# INPUT_OUTPUT.net
KiCad netlist of a schematic drawn in Altium Designer
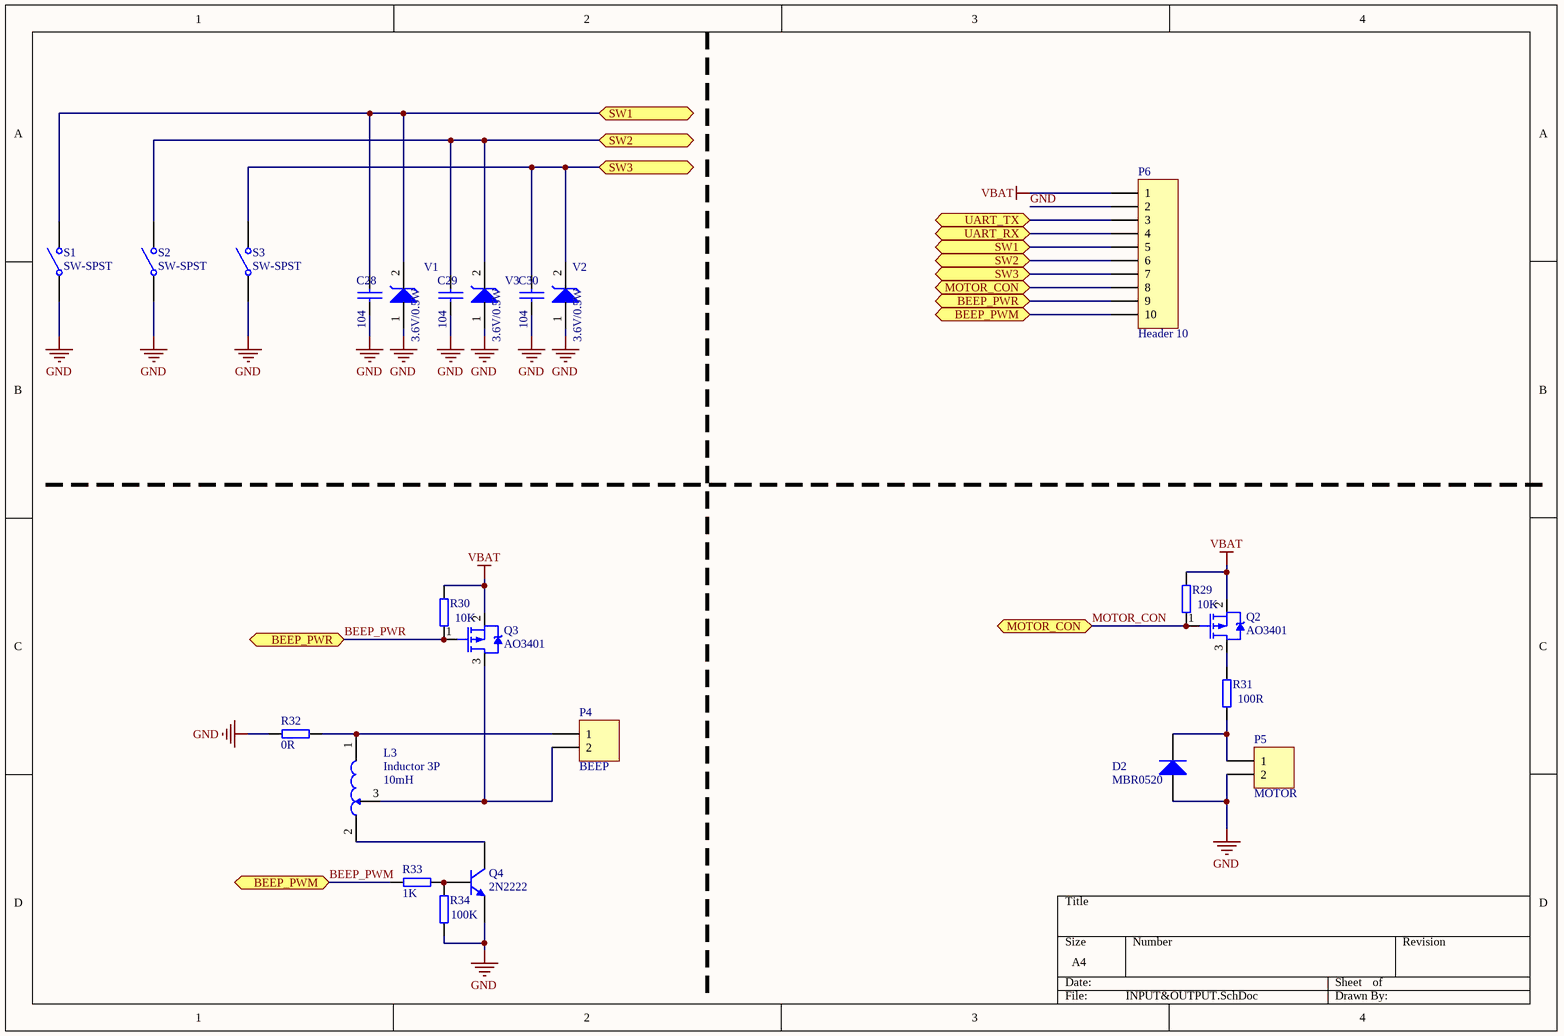
[diagram p0: INPUT&OUTPUT.SchDoc]

(export (version "E")
  (design (tool "Eeschema 10.0.6"))
  (components
    (comp (ref "C28") (value "104") (footprint "0603C") (libsource (lib "WT4815_CPU_Board") (part "0603C")))
    (comp (ref "C29") (value "104") (footprint "0603C") (libsource (lib "WT4815_CPU_Board") (part "0603C")))
    (comp (ref "C30") (value "104") (footprint "0603C") (libsource (lib "WT4815_CPU_Board") (part "0603C")))
    (comp (ref "D2")
      (value "MBR0520")
      (footprint "1206D")
      (description "Default Diode")
      (fields (field (name "PUBLISHER") "Altium Limited"))
      (libsource (lib "*") (part "Diode"))
    )
    (comp (ref "L3")
      (value "Inductor 3P")
      (footprint "HDR1X3 W")
      (description "Adjustable Magnetic-Core Inductor")
      (fields (field (name "ALTIUM_VALUE") "10mH") (field (name "PUBLISHER") "Altium Limited"))
      (libsource (lib "BLE") (part "Inductor 3P"))
    )
    (comp (ref "P4")
      (value "BEEP")
      (footprint "XH2.54-2P")
      (description "Header, 2-Pin")
      (fields (field (name "PUBLISHER") "Altium Limited"))
      (libsource (lib "Miscellaneous Connectors") (part "MHDR1X2"))
    )
    (comp (ref "P5")
      (value "MOTOR")
      (footprint "XH2.54-2P")
      (description "Header, 2-Pin")
      (fields (field (name "PUBLISHER") "Altium Limited"))
      (libsource (lib "Miscellaneous Connectors") (part "MHDR1X2"))
    )
    (comp (ref "P6")
      (value "Header 10")
      (footprint "HDR1X10")
      (description "Header, 10-Pin")
      (fields (field (name "PUBLISHER") "Altium Limited"))
      (libsource (lib "Miscellaneous Connectors") (part "Header 10"))
    )
    (comp (ref "Q2")
      (value "AO3401")
      (footprint "sot23")
      (description "HEXFET Power MOSFET")
      (fields (field (name "PUBLISHER") "*"))
      (libsource (lib "*") (part "IRF5NJ5305"))
    )
    (comp (ref "Q3")
      (value "AO3401")
      (footprint "SOT23")
      (description "HEXFET Power MOSFET")
      (fields (field (name "PUBLISHER") "*"))
      (libsource (lib "*") (part "IRF5NJ5305"))
    )
    (comp (ref "Q4")
      (value "2N2222")
      (footprint "sot23")
      (description "NPN General Purpose Amplifier")
      (fields (field (name "PUBLISHER") "Altium Limited"))
      (libsource (lib "Schlib") (part "2N3904"))
    )
    (comp (ref "R29") (value "10K") (footprint "0603R") (libsource (lib "dtu02") (part "RES2A")))
    (comp (ref "R30") (value "10K") (footprint "0603R") (libsource (lib "dtu02") (part "RES2A")))
    (comp (ref "R31") (value "100R") (footprint "0603R") (libsource (lib "dtu02") (part "RES2A")))
    (comp (ref "R32") (value "0R") (footprint "0603R") (libsource (lib "dtu02") (part "RES2A")))
    (comp (ref "R33") (value "1K") (footprint "0603R") (libsource (lib "dtu02") (part "RES2A")))
    (comp (ref "R34") (value "100K") (footprint "0603R") (libsource (lib "dtu02") (part "RES2A")))
    (comp (ref "S1")
      (value "SW-SPST")
      (footprint "XH2.54-2P")
      (description "Single-Pole, Single-Throw Switch")
      (fields (field (name "PUBLISHER") "Altium Limited"))
      (libsource (lib "Miscellaneous Devices") (part "SW-SPST"))
    )
    (comp (ref "S2")
      (value "SW-SPST")
      (footprint "XH2.54-2P")
      (description "Single-Pole, Single-Throw Switch")
      (fields (field (name "PUBLISHER") "Altium Limited"))
      (libsource (lib "Miscellaneous Devices") (part "SW-SPST"))
    )
    (comp (ref "S3")
      (value "SW-SPST")
      (footprint "XH2.54-2P")
      (description "Single-Pole, Single-Throw Switch")
      (fields (field (name "PUBLISHER") "Altium Limited"))
      (libsource (lib "Miscellaneous Devices") (part "SW-SPST"))
    )
    (comp (ref "V1")
      (value "3.6V/0.5W")
      (footprint "1206D")
      (description "DIODE SCHOTTKY")
      (libsource (lib "*") (part "DIODE-SCHOTTKY"))
    )
    (comp (ref "V2")
      (value "3.6V/0.5W")
      (footprint "1206D")
      (description "DIODE SCHOTTKY")
      (libsource (lib "*") (part "DIODE-SCHOTTKY"))
    )
    (comp (ref "V3")
      (value "3.6V/0.5W")
      (footprint "1206D")
      (description "DIODE SCHOTTKY")
      (libsource (lib "*") (part "DIODE-SCHOTTKY"))
    )
  )
  (nets
    (net (code "2") (name "/BEEP_PWM") (class "Default")
      (node (ref "P6") (pin "10") (pinfunction "10_10") (pintype "passive"))
      (node (ref "R33") (pin "1") (pintype "passive"))
    )
    (net (code "3") (name "/BEEP_PWR") (class "Default")
      (node (ref "P6") (pin "9") (pinfunction "9_9") (pintype "passive"))
      (node (ref "Q3") (pin "1") (pinfunction "G_1") (pintype "passive"))
      (node (ref "R30") (pin "2") (pintype "passive"))
    )
    (net (code "4") (name "/MOTOR_CON") (class "Default")
      (node (ref "P6") (pin "8") (pinfunction "8_8") (pintype "passive"))
      (node (ref "Q2") (pin "1") (pinfunction "G_1") (pintype "passive"))
      (node (ref "R29") (pin "2") (pintype "passive"))
    )
    (net (code "5") (name "/SW1") (class "Default")
      (node (ref "C28") (pin "1") (pintype "passive"))
      (node (ref "P6") (pin "5") (pinfunction "5_5") (pintype "passive"))
      (node (ref "S1") (pin "2") (pinfunction "NO_2") (pintype "passive"))
      (node (ref "V1") (pin "2") (pinfunction "2_2") (pintype "passive"))
    )
    (net (code "6") (name "/SW2") (class "Default")
      (node (ref "C29") (pin "1") (pintype "passive"))
      (node (ref "P6") (pin "6") (pinfunction "6_6") (pintype "passive"))
      (node (ref "S2") (pin "2") (pinfunction "NO_2") (pintype "passive"))
      (node (ref "V3") (pin "2") (pinfunction "2_2") (pintype "passive"))
    )
    (net (code "7") (name "/SW3") (class "Default")
      (node (ref "C30") (pin "1") (pintype "passive"))
      (node (ref "P6") (pin "7") (pinfunction "7_7") (pintype "passive"))
      (node (ref "S3") (pin "2") (pinfunction "NO_2") (pintype "passive"))
      (node (ref "V2") (pin "2") (pinfunction "2_2") (pintype "passive"))
    )
    (net (code "8") (name "/UART_RX") (class "Default")
      (node (ref "P6") (pin "4") (pinfunction "4_4") (pintype "passive"))
    )
    (net (code "9") (name "/UART_TX") (class "Default")
      (node (ref "P6") (pin "3") (pinfunction "3_3") (pintype "passive"))
    )
    (net (code "10") (name "GND") (class "Default")
      (node (ref "C28") (pin "2") (pintype "passive"))
      (node (ref "C29") (pin "2") (pintype "passive"))
      (node (ref "C30") (pin "2") (pintype "passive"))
      (node (ref "D2") (pin "1") (pinfunction "A_1") (pintype "passive"))
      (node (ref "P5") (pin "2") (pinfunction "2_2") (pintype "passive"))
      (node (ref "P6") (pin "2") (pinfunction "2_2") (pintype "passive"))
      (node (ref "Q4") (pin "1") (pinfunction "E_1") (pintype "passive"))
      (node (ref "R32") (pin "1") (pintype "passive"))
      (node (ref "R34") (pin "2") (pintype "passive"))
      (node (ref "S1") (pin "1") (pinfunction "COMMON_1") (pintype "passive"))
      (node (ref "S2") (pin "1") (pinfunction "COMMON_1") (pintype "passive"))
      (node (ref "S3") (pin "1") (pinfunction "COMMON_1") (pintype "passive"))
      (node (ref "V1") (pin "1") (pinfunction "1_1") (pintype "passive"))
      (node (ref "V2") (pin "1") (pinfunction "1_1") (pintype "passive"))
      (node (ref "V3") (pin "1") (pinfunction "1_1") (pintype "passive"))
    )
    (net (code "11") (name "Net-(D2-K)") (class "Default")
      (node (ref "D2") (pin "2") (pinfunction "K_2") (pintype "passive"))
      (node (ref "P5") (pin "1") (pinfunction "1_1") (pintype "passive"))
      (node (ref "R31") (pin "2") (pintype "passive"))
    )
    (net (code "12") (name "Net-(L3-Pad1)") (class "Default")
      (node (ref "L3") (pin "1") (pinfunction "1_1") (pintype "passive"))
      (node (ref "P4") (pin "1") (pinfunction "1_1") (pintype "passive"))
      (node (ref "R32") (pin "2") (pintype "passive"))
    )
    (net (code "13") (name "Net-(Q2-D)") (class "Default")
      (node (ref "Q2") (pin "3") (pinfunction "D_3") (pintype "passive"))
      (node (ref "R31") (pin "1") (pintype "passive"))
    )
    (net (code "14") (name "Net-(Q3-D)") (class "Default")
      (node (ref "L3") (pin "3") (pinfunction "3_3") (pintype "passive"))
      (node (ref "P4") (pin "2") (pinfunction "2_2") (pintype "passive"))
      (node (ref "Q3") (pin "3") (pinfunction "D_3") (pintype "passive"))
    )
    (net (code "15") (name "Net-(Q4-B)") (class "Default")
      (node (ref "Q4") (pin "2") (pinfunction "B_2") (pintype "passive"))
      (node (ref "R33") (pin "2") (pintype "passive"))
      (node (ref "R34") (pin "1") (pintype "passive"))
    )
    (net (code "16") (name "Net-(Q4-C)") (class "Default")
      (node (ref "L3") (pin "2") (pinfunction "2_2") (pintype "passive"))
      (node (ref "Q4") (pin "3") (pinfunction "C_3") (pintype "passive"))
    )
    (net (code "17") (name "VBAT") (class "Default")
      (node (ref "P6") (pin "1") (pinfunction "1_1") (pintype "passive"))
      (node (ref "Q2") (pin "2") (pinfunction "S_2") (pintype "passive"))
      (node (ref "Q3") (pin "2") (pinfunction "S_2") (pintype "passive"))
      (node (ref "R29") (pin "1") (pintype "passive"))
      (node (ref "R30") (pin "1") (pintype "passive"))
    )
  )
)
